# UI_Ticketing_Slave.net
KiCad netlist of a schematic drawn in Altium Designer
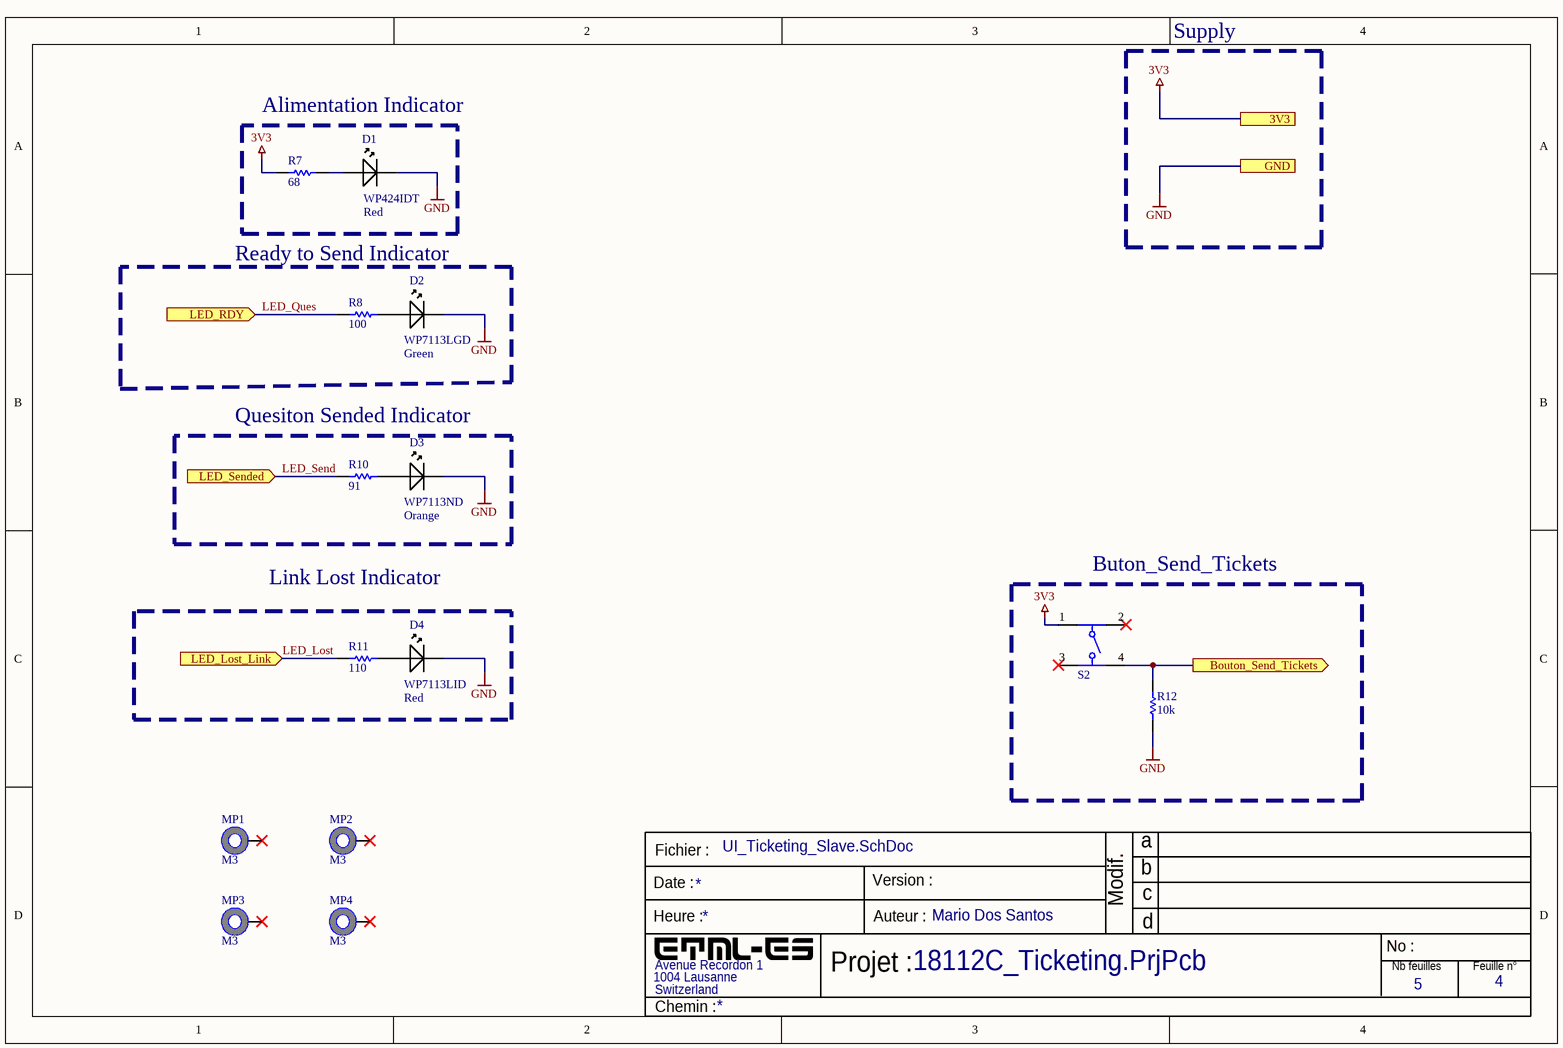
[diagram p0: UI_Ticketing_Slave.SchDoc]

(export (version "E")
  (design (tool "Eeschema 10.0.6"))
  (components
    (comp (ref "D1")
      (value "WP424IDT")
      (footprint "LED-2P-2.28-3MM")
      (description "LED")
      (fields (field (name "COLOR") "Red"))
      (libsource (lib "") (part "LED_1"))
    )
    (comp (ref "D2")
      (value "WP7113LGD")
      (footprint "Type 5mm")
      (description "LED")
      (fields (field (name "COLOR") "Green"))
      (libsource (lib "Spectrometre_Lib") (part "LED"))
    )
    (comp (ref "D3")
      (value "WP7113ND")
      (footprint "Type 5mm")
      (description "LED")
      (fields (field (name "COLOR") "Orange"))
      (libsource (lib "Spectrometre_Lib") (part "LED"))
    )
    (comp (ref "D4")
      (value "WP7113LID")
      (footprint "Type 5mm")
      (description "LED")
      (fields (field (name "COLOR") "Red"))
      (libsource (lib "Spectrometre_Lib") (part "LED"))
    )
    (comp (ref "MP1")
      (value "M3")
      (footprint "9774010151")
      (description "WA-SMSI SMT Steel Spacer, M2.5 Thread Internal, Length 1mm")
      (libsource (lib "ALTIUM-SMSI_SMT_STEEL_SPACER_M2_5_THREAD_INTERNAL-rev16b") (part "9774010151"))
    )
    (comp (ref "MP2")
      (value "M3")
      (footprint "9774010151")
      (description "WA-SMSI SMT Steel Spacer, M2.5 Thread Internal, Length 1mm")
      (libsource (lib "ALTIUM-SMSI_SMT_STEEL_SPACER_M2_5_THREAD_INTERNAL-rev16b") (part "9774010151"))
    )
    (comp (ref "MP3")
      (value "M3")
      (footprint "9774010151")
      (description "WA-SMSI SMT Steel Spacer, M2.5 Thread Internal, Length 1mm")
      (libsource (lib "ALTIUM-SMSI_SMT_STEEL_SPACER_M2_5_THREAD_INTERNAL-rev16b") (part "9774010151"))
    )
    (comp (ref "MP4")
      (value "M3")
      (footprint "9774010151")
      (description "WA-SMSI SMT Steel Spacer, M2.5 Thread Internal, Length 1mm")
      (libsource (lib "ALTIUM-SMSI_SMT_STEEL_SPACER_M2_5_THREAD_INTERNAL-rev16b") (part "9774010151"))
    )
    (comp (ref "R7")
      (value "68")
      (footprint "RESC0805(2012)_L")
      (description "100K 0.125W 5% 0805 (2012 Metric)  SMD")
      (libsource (lib "Altium Content Vault") (part "CMP-1013-00122-1"))
    )
    (comp (ref "R8")
      (value "100")
      (footprint "RESC0805(2012)_L")
      (description "100K 0.125W 5% 0805 (2012 Metric)  SMD")
      (libsource (lib "Altium Content Vault") (part "CMP-1013-00122-1"))
    )
    (comp (ref "R10")
      (value "91")
      (footprint "RESC0805(2012)_L")
      (description "100K 0.125W 5% 0805 (2012 Metric)  SMD")
      (libsource (lib "Altium Content Vault") (part "CMP-1013-00122-1"))
    )
    (comp (ref "R11")
      (value "110")
      (footprint "RESC0805(2012)_L")
      (description "100K 0.125W 5% 0805 (2012 Metric)  SMD")
      (libsource (lib "Altium Content Vault") (part "CMP-1013-00122-1"))
    )
    (comp (ref "R12")
      (value "10k")
      (footprint "RESC0805(2012)_L")
      (description "100K 0.125W 5% 0805 (2012 Metric)  SMD")
      (libsource (lib "Altium Content Vault") (part "CMP-1013-00122-1"))
    )
    (comp (ref "S2")
      (value "430466073726")
      (footprint "4304x60737x6_12x12x7.3")
      (description "WS-TATV 12x12mm washable Tact Switch, THT version")
      (libsource (lib "ALTIUM-WS-TATV-rev17a") (part "430466073726"))
    )
  )
  (nets
    (net (code "1") (name "/Bouton_Send_Tickets") (class "Default")
      (node (ref "R12") (pin "1") (pinfunction "1_1") (pintype "passive"))
      (node (ref "S2") (pin "4") (pinfunction "4_4") (pintype "passive"))
    )
    (net (code "2") (name "/LED_Lost") (class "Default")
      (node (ref "R11") (pin "2") (pinfunction "2_2") (pintype "passive"))
    )
    (net (code "3") (name "/LED_Ques") (class "Default")
      (node (ref "R8") (pin "2") (pinfunction "2_2") (pintype "passive"))
    )
    (net (code "4") (name "/LED_Send") (class "Default")
      (node (ref "R10") (pin "2") (pinfunction "2_2") (pintype "passive"))
    )
    (net (code "5") (name "3V3") (class "Default")
      (node (ref "R7") (pin "2") (pinfunction "2_2") (pintype "passive"))
      (node (ref "S2") (pin "1") (pinfunction "1_1") (pintype "passive"))
    )
    (net (code "6") (name "GND") (class "Default")
      (node (ref "D1") (pin "2") (pinfunction "Cathode_2") (pintype "passive"))
      (node (ref "D2") (pin "1") (pinfunction "Cathode_1") (pintype "passive"))
      (node (ref "D3") (pin "1") (pinfunction "Cathode_1") (pintype "passive"))
      (node (ref "D4") (pin "1") (pinfunction "Cathode_1") (pintype "passive"))
      (node (ref "R12") (pin "2") (pinfunction "2_2") (pintype "passive"))
    )
    (net (code "7") (name "Net-(D1-Anode)") (class "Default")
      (node (ref "D1") (pin "1") (pinfunction "Anode_1") (pintype "passive"))
      (node (ref "R7") (pin "1") (pinfunction "1_1") (pintype "passive"))
    )
    (net (code "8") (name "Net-(D2-Anode)") (class "Default")
      (node (ref "D2") (pin "2") (pinfunction "Anode_2") (pintype "passive"))
      (node (ref "R8") (pin "1") (pinfunction "1_1") (pintype "passive"))
    )
    (net (code "9") (name "Net-(D3-Anode)") (class "Default")
      (node (ref "D3") (pin "2") (pinfunction "Anode_2") (pintype "passive"))
      (node (ref "R10") (pin "1") (pinfunction "1_1") (pintype "passive"))
    )
    (net (code "10") (name "Net-(D4-Anode)") (class "Default")
      (node (ref "D4") (pin "2") (pinfunction "Anode_2") (pintype "passive"))
      (node (ref "R11") (pin "1") (pinfunction "1_1") (pintype "passive"))
    )
    (net (code "11") (name "unconnected-(MP1-Pad1)") (class "Default")
      (node (ref "MP1") (pin "1") (pinfunction "1_1") (pintype "passive+no_connect"))
    )
    (net (code "12") (name "unconnected-(MP2-Pad1)") (class "Default")
      (node (ref "MP2") (pin "1") (pinfunction "1_1") (pintype "passive+no_connect"))
    )
    (net (code "13") (name "unconnected-(MP3-Pad1)") (class "Default")
      (node (ref "MP3") (pin "1") (pinfunction "1_1") (pintype "passive+no_connect"))
    )
    (net (code "14") (name "unconnected-(MP4-Pad1)") (class "Default")
      (node (ref "MP4") (pin "1") (pinfunction "1_1") (pintype "passive+no_connect"))
    )
    (net (code "15") (name "unconnected-(S2-Pad2)") (class "Default")
      (node (ref "S2") (pin "2") (pinfunction "2_2") (pintype "passive+no_connect"))
    )
    (net (code "16") (name "unconnected-(S2-Pad3)") (class "Default")
      (node (ref "S2") (pin "3") (pinfunction "3_3") (pintype "passive+no_connect"))
    )
  )
)
